# cpu.net
KiCad netlist of a schematic drawn in EAGLE
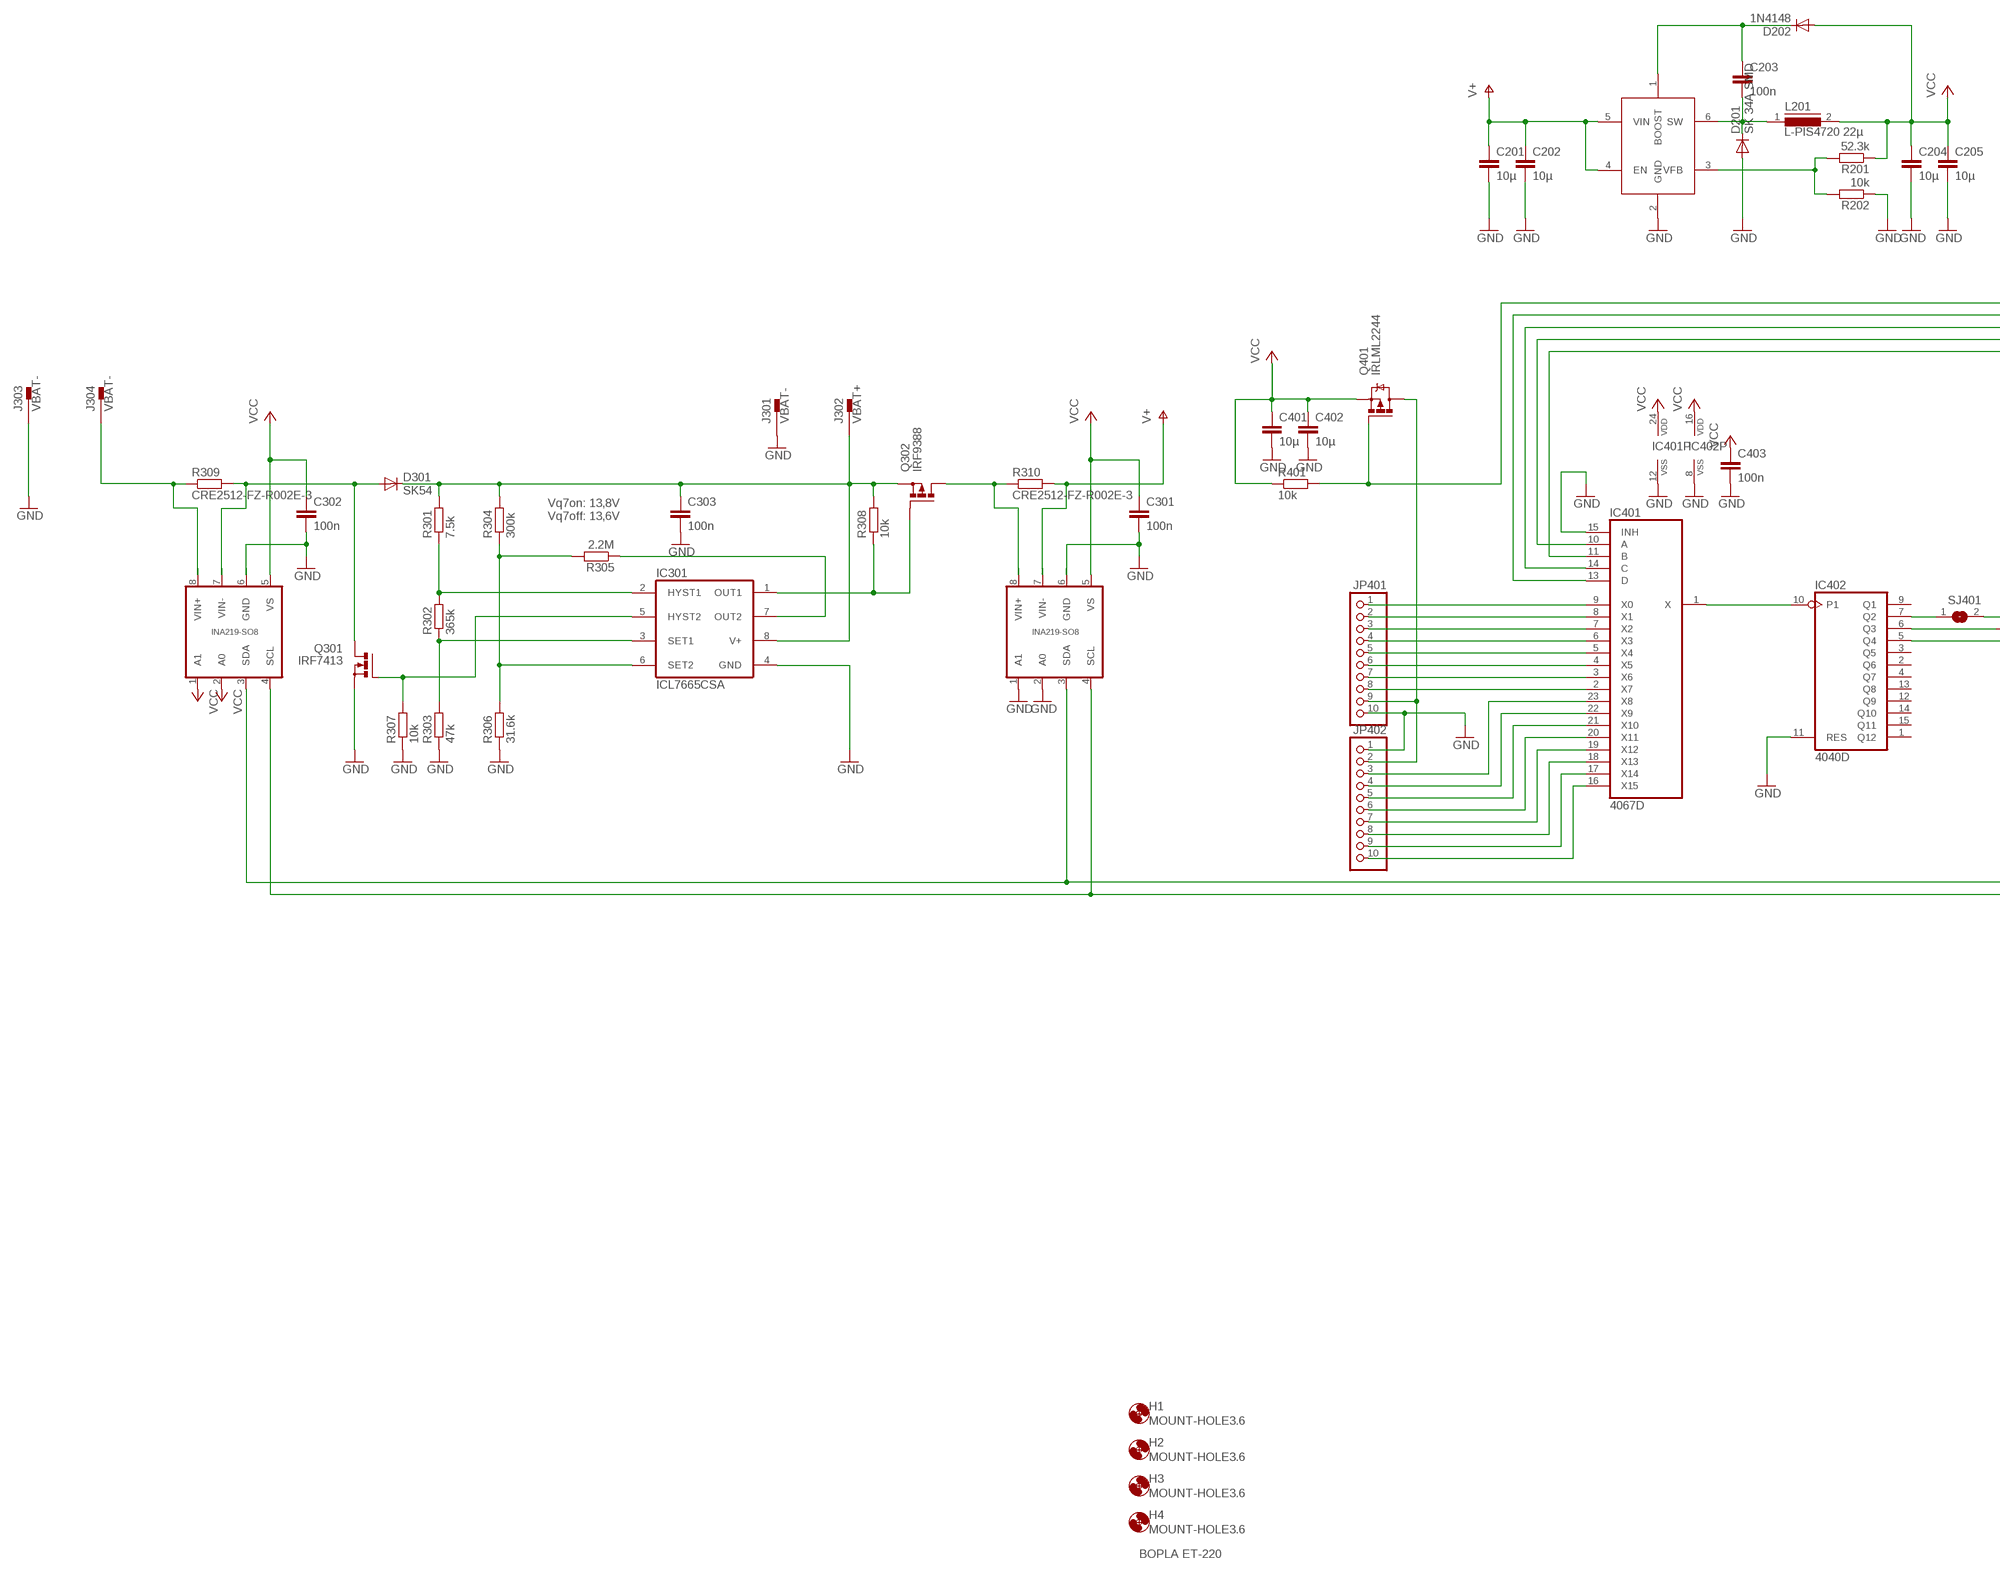
[diagram p0: schematic, sheet 1, part 1 of 2]
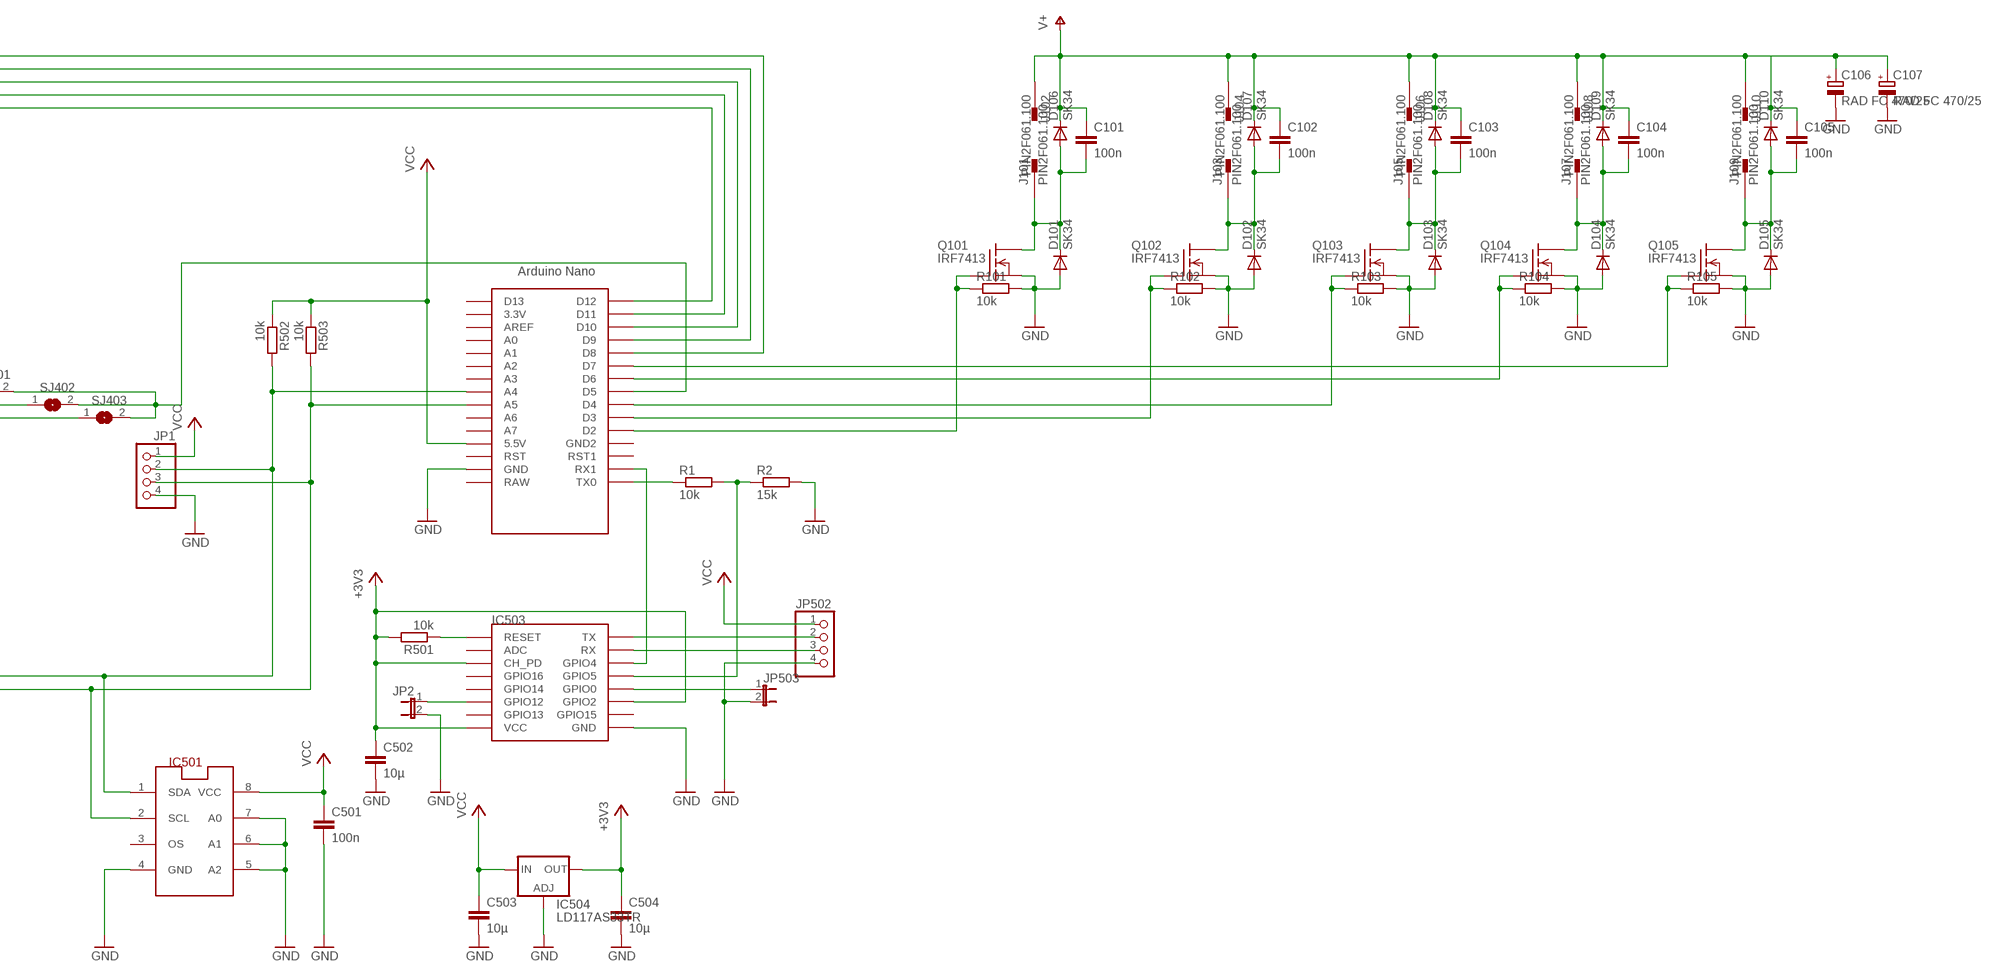
[diagram p1: schematic, sheet 1, part 2 of 2]

(export (version "E")
  (design (tool "Eeschema 10.0.6"))
  (components
    (comp (ref "C101")
      (value "100n")
      (footprint "eagle-import:C1206")
      (libsource (lib "eagle-import") (part "C-EUC1206"))
    )
    (comp (ref "C102")
      (value "100n")
      (footprint "eagle-import:C1206")
      (libsource (lib "eagle-import") (part "C-EUC1206"))
    )
    (comp (ref "C103")
      (value "100n")
      (footprint "eagle-import:C1206")
      (libsource (lib "eagle-import") (part "C-EUC1206"))
    )
    (comp (ref "C104")
      (value "100n")
      (footprint "eagle-import:C1206")
      (libsource (lib "eagle-import") (part "C-EUC1206"))
    )
    (comp (ref "C105")
      (value "100n")
      (footprint "eagle-import:C1206")
      (libsource (lib "eagle-import") (part "C-EUC1206"))
    )
    (comp (ref "C106")
      (value "RAD FC 470/25")
      (footprint "eagle-import:E3,5-8")
      (libsource (lib "eagle-import") (part "CPOL-EUE3.5-8"))
    )
    (comp (ref "C107")
      (value "RAD FC 470/25")
      (footprint "eagle-import:E3,5-8")
      (libsource (lib "eagle-import") (part "CPOL-EUE3.5-8"))
    )
    (comp (ref "C201")
      (value "10µ")
      (footprint "eagle-import:C1206")
      (libsource (lib "eagle-import") (part "C-EUC1206"))
    )
    (comp (ref "C202")
      (value "10µ")
      (footprint "eagle-import:C1206")
      (libsource (lib "eagle-import") (part "C-EUC1206"))
    )
    (comp (ref "C203")
      (value "100n")
      (footprint "eagle-import:C1206")
      (libsource (lib "eagle-import") (part "C-EUC1206"))
    )
    (comp (ref "C204")
      (value "10µ")
      (footprint "eagle-import:C1206")
      (libsource (lib "eagle-import") (part "C-EUC1206"))
    )
    (comp (ref "C205")
      (value "10µ")
      (footprint "eagle-import:C1206")
      (libsource (lib "eagle-import") (part "C-EUC1206"))
    )
    (comp (ref "C301")
      (value "100n")
      (footprint "eagle-import:C1206")
      (libsource (lib "eagle-import") (part "C-EUC1206"))
    )
    (comp (ref "C302")
      (value "100n")
      (footprint "eagle-import:C1206")
      (libsource (lib "eagle-import") (part "C-EUC1206"))
    )
    (comp (ref "C303")
      (value "100n")
      (footprint "eagle-import:C1206")
      (libsource (lib "eagle-import") (part "C-EUC1206"))
    )
    (comp (ref "C401")
      (value "10µ")
      (footprint "eagle-import:C1206")
      (libsource (lib "eagle-import") (part "C-EUC1206"))
    )
    (comp (ref "C402")
      (value "10µ")
      (footprint "eagle-import:C1206")
      (libsource (lib "eagle-import") (part "C-EUC1206"))
    )
    (comp (ref "C403")
      (value "100n")
      (footprint "eagle-import:C1206")
      (libsource (lib "eagle-import") (part "C-EUC1206"))
    )
    (comp (ref "C501")
      (value "100n")
      (footprint "eagle-import:C1206")
      (libsource (lib "eagle-import") (part "C-EUC1206"))
    )
    (comp (ref "C502")
      (value "10µ")
      (footprint "eagle-import:C1206")
      (libsource (lib "eagle-import") (part "C-EUC1206"))
    )
    (comp (ref "C503")
      (value "10µ")
      (footprint "eagle-import:C1206")
      (libsource (lib "eagle-import") (part "C-EUC1206"))
    )
    (comp (ref "C504")
      (value "10µ")
      (footprint "eagle-import:C1206")
      (libsource (lib "eagle-import") (part "C-EUC1206"))
    )
    (comp (ref "D101")
      (value "SK34")
      (footprint "eagle-import:DO214BA")
      (libsource (lib "eagle-import") (part "DIODE-DO214BA"))
    )
    (comp (ref "D102")
      (value "SK34")
      (footprint "eagle-import:DO214BA")
      (libsource (lib "eagle-import") (part "DIODE-DO214BA"))
    )
    (comp (ref "D103")
      (value "SK34")
      (footprint "eagle-import:DO214BA")
      (libsource (lib "eagle-import") (part "DIODE-DO214BA"))
    )
    (comp (ref "D104")
      (value "SK34")
      (footprint "eagle-import:DO214BA")
      (libsource (lib "eagle-import") (part "DIODE-DO214BA"))
    )
    (comp (ref "D105")
      (value "SK34")
      (footprint "eagle-import:DO214BA")
      (libsource (lib "eagle-import") (part "DIODE-DO214BA"))
    )
    (comp (ref "D106")
      (value "SK34")
      (footprint "eagle-import:DO214BA")
      (libsource (lib "eagle-import") (part "DIODE-DO214BA"))
    )
    (comp (ref "D107")
      (value "SK34")
      (footprint "eagle-import:DO214BA")
      (libsource (lib "eagle-import") (part "DIODE-DO214BA"))
    )
    (comp (ref "D108")
      (value "SK34")
      (footprint "eagle-import:DO214BA")
      (libsource (lib "eagle-import") (part "DIODE-DO214BA"))
    )
    (comp (ref "D109")
      (value "SK34")
      (footprint "eagle-import:DO214BA")
      (libsource (lib "eagle-import") (part "DIODE-DO214BA"))
    )
    (comp (ref "D110")
      (value "SK34")
      (footprint "eagle-import:DO214BA")
      (libsource (lib "eagle-import") (part "DIODE-DO214BA"))
    )
    (comp (ref "D201")
      (value "SK 34A SMD")
      (footprint "eagle-import:DO214BA")
      (libsource (lib "eagle-import") (part "DIODE-DO214BA"))
    )
    (comp (ref "D202")
      (value "1N4148")
      (footprint "eagle-import:MINIMELF")
      (libsource (lib "eagle-import") (part "DIODE-MINIMELF"))
    )
    (comp (ref "D301")
      (value "SK54")
      (footprint "eagle-import:SMC")
      (libsource (lib "eagle-import") (part "DIODE-SMC"))
    )
    (comp (ref "H1")
      (value "MOUNT-HOLE3.6")
      (footprint "eagle-import:3,6")
      (libsource (lib "eagle-import") (part "MOUNT-HOLE3.6"))
    )
    (comp (ref "H2")
      (value "MOUNT-HOLE3.6")
      (footprint "eagle-import:3,6")
      (libsource (lib "eagle-import") (part "MOUNT-HOLE3.6"))
    )
    (comp (ref "H3")
      (value "MOUNT-HOLE3.6")
      (footprint "eagle-import:3,6")
      (libsource (lib "eagle-import") (part "MOUNT-HOLE3.6"))
    )
    (comp (ref "H4")
      (value "MOUNT-HOLE3.6")
      (footprint "eagle-import:3,6")
      (libsource (lib "eagle-import") (part "MOUNT-HOLE3.6"))
    )
    (comp (ref "IC201")
      (value "MCP16301/H")
      (footprint "eagle-import:SOT23-6")
      (libsource (lib "eagle-import") (part "MCP16301/H"))
    )
    (comp (ref "IC301")
      (value "ICL7665CSA")
      (footprint "eagle-import:SO08")
      (fields (field (name "MPN") "ICL7665CSA+"))
      (libsource (lib "eagle-import") (part "ICL7665CSA"))
    )
    (comp (ref "IC302")
      (value "INA219-SO8D")
      (footprint "eagle-import:SO08")
      (libsource (lib "eagle-import") (part "INA219-SO8D"))
    )
    (comp (ref "IC303")
      (value "INA219-SO8D")
      (footprint "eagle-import:SO08")
      (libsource (lib "eagle-import") (part "INA219-SO8D"))
    )
    (comp (ref "IC401")
      (value "4067D")
      (footprint "eagle-import:SO24W")
      (libsource (lib "eagle-import") (part "4067D"))
    )
    (comp (ref "IC402")
      (value "4040D")
      (footprint "eagle-import:SO16")
      (libsource (lib "eagle-import") (part "4040D"))
    )
    (comp (ref "IC501")
      (value "LM75_ICN")
      (footprint "eagle-import:SO8_LM75")
      (libsource (lib "eagle-import") (part "LM75_ICN"))
    )
    (comp (ref "IC502")
      (value "NANO")
      (footprint "eagle-import:NANO")
      (libsource (lib "eagle-import") (part "NANO"))
    )
    (comp (ref "IC503")
      (value "ESP12SMD")
      (footprint "eagle-import:ESP12-SMD")
      (libsource (lib "eagle-import") (part "ESP12SMD"))
    )
    (comp (ref "IC504")
      (value "LD117AS33TR")
      (footprint "eagle-import:SOT223")
      (libsource (lib "eagle-import") (part "LD117A?S33TR"))
    )
    (comp (ref "J101")
      (value "PIN2F061.100")
      (footprint "eagle-import:F061.100")
      (libsource (lib "eagle-import") (part "PIN2F061.100"))
    )
    (comp (ref "J102")
      (value "PIN2F061.100")
      (footprint "eagle-import:F061.100")
      (fields (field (name "OC_FARNELL") "unknown") (field (name "OC_NEWARK") "unknown"))
      (libsource (lib "eagle-import") (part "PIN2F061.100"))
    )
    (comp (ref "J103")
      (value "PIN2F061.100")
      (footprint "eagle-import:F061.100")
      (libsource (lib "eagle-import") (part "PIN2F061.100"))
    )
    (comp (ref "J104")
      (value "PIN2F061.100")
      (footprint "eagle-import:F061.100")
      (fields (field (name "OC_FARNELL") "unknown") (field (name "OC_NEWARK") "unknown"))
      (libsource (lib "eagle-import") (part "PIN2F061.100"))
    )
    (comp (ref "J105")
      (value "PIN2F061.100")
      (footprint "eagle-import:F061.100")
      (libsource (lib "eagle-import") (part "PIN2F061.100"))
    )
    (comp (ref "J106")
      (value "PIN2F061.100")
      (footprint "eagle-import:F061.100")
      (fields (field (name "OC_FARNELL") "unknown") (field (name "OC_NEWARK") "unknown"))
      (libsource (lib "eagle-import") (part "PIN2F061.100"))
    )
    (comp (ref "J107")
      (value "PIN2F061.100")
      (footprint "eagle-import:F061.100")
      (libsource (lib "eagle-import") (part "PIN2F061.100"))
    )
    (comp (ref "J108")
      (value "PIN2F061.100")
      (footprint "eagle-import:F061.100")
      (fields (field (name "OC_FARNELL") "unknown") (field (name "OC_NEWARK") "unknown"))
      (libsource (lib "eagle-import") (part "PIN2F061.100"))
    )
    (comp (ref "J109")
      (value "PIN2F061.100")
      (footprint "eagle-import:F061.100")
      (libsource (lib "eagle-import") (part "PIN2F061.100"))
    )
    (comp (ref "J110")
      (value "PIN2F061.100")
      (footprint "eagle-import:F061.100")
      (fields (field (name "OC_FARNELL") "unknown") (field (name "OC_NEWARK") "unknown"))
      (libsource (lib "eagle-import") (part "PIN2F061.100"))
    )
    (comp (ref "J301")
      (value "VBAT-")
      (footprint "eagle-import:F061.100")
      (fields (field (name "OC_FARNELL") "unknown") (field (name "OC_NEWARK") "unknown"))
      (libsource (lib "eagle-import") (part "PIN2F061.100"))
    )
    (comp (ref "J302")
      (value "VBAT+")
      (footprint "eagle-import:F061.100")
      (fields (field (name "OC_FARNELL") "unknown") (field (name "OC_NEWARK") "unknown"))
      (libsource (lib "eagle-import") (part "PIN2F061.100"))
    )
    (comp (ref "J303")
      (value "VBAT-")
      (footprint "eagle-import:F061.100")
      (fields (field (name "OC_FARNELL") "unknown") (field (name "OC_NEWARK") "unknown"))
      (libsource (lib "eagle-import") (part "PIN2F061.100"))
    )
    (comp (ref "J304")
      (value "VBAT-")
      (footprint "eagle-import:F061.100")
      (fields (field (name "OC_FARNELL") "unknown") (field (name "OC_NEWARK") "unknown"))
      (libsource (lib "eagle-import") (part "PIN2F061.100"))
    )
    (comp (ref "JP1")
      (value "PINHD-1X4")
      (footprint "eagle-import:1X04")
      (libsource (lib "eagle-import") (part "PINHD-1X4"))
    )
    (comp (ref "JP2")
      (value "JP1E")
      (footprint "eagle-import:JP1")
      (libsource (lib "eagle-import") (part "JP1E"))
    )
    (comp (ref "JP401")
      (value "PINHD-1X10")
      (footprint "eagle-import:1X10")
      (libsource (lib "eagle-import") (part "PINHD-1X10"))
    )
    (comp (ref "JP402")
      (value "PINHD-1X10")
      (footprint "eagle-import:1X10")
      (libsource (lib "eagle-import") (part "PINHD-1X10"))
    )
    (comp (ref "JP502")
      (value "PINHD-1X4")
      (footprint "eagle-import:1X04")
      (libsource (lib "eagle-import") (part "PINHD-1X4"))
    )
    (comp (ref "JP503")
      (value "JP1E")
      (footprint "eagle-import:JP1")
      (libsource (lib "eagle-import") (part "JP1E"))
    )
    (comp (ref "L201")
      (value "L-PIS4720 22µ")
      (footprint "eagle-import:DR74")
      (libsource (lib "eagle-import") (part "DR74"))
    )
    (comp (ref "Q101")
      (value "IRF7413")
      (footprint "eagle-import:SO-8")
      (libsource (lib "eagle-import") (part "FDS5680"))
    )
    (comp (ref "Q102")
      (value "IRF7413")
      (footprint "eagle-import:SO-8")
      (libsource (lib "eagle-import") (part "FDS5680"))
    )
    (comp (ref "Q103")
      (value "IRF7413")
      (footprint "eagle-import:SO-8")
      (libsource (lib "eagle-import") (part "FDS5680"))
    )
    (comp (ref "Q104")
      (value "IRF7413")
      (footprint "eagle-import:SO-8")
      (libsource (lib "eagle-import") (part "FDS5680"))
    )
    (comp (ref "Q105")
      (value "IRF7413")
      (footprint "eagle-import:SO-8")
      (libsource (lib "eagle-import") (part "FDS5680"))
    )
    (comp (ref "Q301")
      (value "IRF7413")
      (footprint "eagle-import:SO-08")
      (libsource (lib "eagle-import") (part "N-MOSFET-SO8S"))
    )
    (comp (ref "Q302")
      (value "IRF9388")
      (footprint "eagle-import:SO-08")
      (libsource (lib "eagle-import") (part "P-MOSFET-SO8"))
    )
    (comp (ref "Q401")
      (value "IRLML2244")
      (footprint "eagle-import:MICRO3")
      (libsource (lib "eagle-import") (part "IRLML5203"))
    )
    (comp (ref "R1")
      (value "10k")
      (footprint "eagle-import:R0805")
      (libsource (lib "eagle-import") (part "R-EU_R0805"))
    )
    (comp (ref "R2")
      (value "15k")
      (footprint "eagle-import:R0805")
      (libsource (lib "eagle-import") (part "R-EU_R0805"))
    )
    (comp (ref "R101")
      (value "10k")
      (footprint "eagle-import:R0805")
      (libsource (lib "eagle-import") (part "R-EU_R0805"))
    )
    (comp (ref "R102")
      (value "10k")
      (footprint "eagle-import:R0805")
      (libsource (lib "eagle-import") (part "R-EU_R0805"))
    )
    (comp (ref "R103")
      (value "10k")
      (footprint "eagle-import:R0805")
      (libsource (lib "eagle-import") (part "R-EU_R0805"))
    )
    (comp (ref "R104")
      (value "10k")
      (footprint "eagle-import:R0805")
      (libsource (lib "eagle-import") (part "R-EU_R0805"))
    )
    (comp (ref "R105")
      (value "10k")
      (footprint "eagle-import:R0805")
      (libsource (lib "eagle-import") (part "R-EU_R0805"))
    )
    (comp (ref "R201")
      (value "52.3k")
      (footprint "eagle-import:R0805")
      (libsource (lib "eagle-import") (part "R-EU_R0805"))
    )
    (comp (ref "R202")
      (value "10k")
      (footprint "eagle-import:R0805")
      (libsource (lib "eagle-import") (part "R-EU_R0805"))
    )
    (comp (ref "R301")
      (value "7.5k")
      (footprint "eagle-import:R0805")
      (libsource (lib "eagle-import") (part "R-EU_R0805"))
    )
    (comp (ref "R302")
      (value "365k")
      (footprint "eagle-import:R0805")
      (libsource (lib "eagle-import") (part "R-EU_R0805"))
    )
    (comp (ref "R303")
      (value "47k")
      (footprint "eagle-import:R0805")
      (libsource (lib "eagle-import") (part "R-EU_R0805"))
    )
    (comp (ref "R304")
      (value "300k")
      (footprint "eagle-import:R0805")
      (libsource (lib "eagle-import") (part "R-EU_R0805"))
    )
    (comp (ref "R305")
      (value "2.2M")
      (footprint "eagle-import:R0805")
      (libsource (lib "eagle-import") (part "R-EU_R0805"))
    )
    (comp (ref "R306")
      (value "31.6k")
      (footprint "eagle-import:R0805")
      (libsource (lib "eagle-import") (part "R-EU_R0805"))
    )
    (comp (ref "R307")
      (value "10k")
      (footprint "eagle-import:R0805")
      (libsource (lib "eagle-import") (part "R-EU_R0805"))
    )
    (comp (ref "R308")
      (value "10k")
      (footprint "eagle-import:R0805")
      (libsource (lib "eagle-import") (part "R-EU_R0805"))
    )
    (comp (ref "R309")
      (value "CRE2512-FZ-R002E-3")
      (footprint "eagle-import:R2512")
      (libsource (lib "eagle-import") (part "R-EU_R2512"))
    )
    (comp (ref "R310")
      (value "CRE2512-FZ-R002E-3")
      (footprint "eagle-import:R2512")
      (libsource (lib "eagle-import") (part "R-EU_R2512"))
    )
    (comp (ref "R401")
      (value "10k")
      (footprint "eagle-import:R0805")
      (libsource (lib "eagle-import") (part "R-EU_R0805"))
    )
    (comp (ref "R501")
      (value "10k")
      (footprint "eagle-import:R0805")
      (libsource (lib "eagle-import") (part "R-EU_R0805"))
    )
    (comp (ref "R502")
      (value "10k")
      (footprint "eagle-import:R0805")
      (libsource (lib "eagle-import") (part "R-EU_R0805"))
    )
    (comp (ref "R503")
      (value "10k")
      (footprint "eagle-import:R0805")
      (libsource (lib "eagle-import") (part "R-EU_R0805"))
    )
    (comp (ref "SJ401")
      (value "SJW")
      (footprint "eagle-import:SJW")
      (libsource (lib "eagle-import") (part "SJW"))
    )
    (comp (ref "SJ402")
      (value "SJW")
      (footprint "eagle-import:SJW")
      (libsource (lib "eagle-import") (part "SJW"))
    )
    (comp (ref "SJ403")
      (value "SJW")
      (footprint "eagle-import:SJW")
      (libsource (lib "eagle-import") (part "SJW"))
    )
  )
  (nets
    (net (code "1") (name "+3V3") (class "Default")
      (node (ref "C502") (pin "1") (pinfunction "1_1") (pintype "passive"))
      (node (ref "C504") (pin "1") (pinfunction "1_1") (pintype "passive"))
      (node (ref "IC503") (pin "CH_PD") (pinfunction "CH_PD_CH_PD") (pintype "bidirectional"))
      (node (ref "IC503") (pin "GPIO2") (pinfunction "GPIO2_GPIO2") (pintype "bidirectional"))
      (node (ref "IC503") (pin "VCC") (pinfunction "VCC_VCC") (pintype "bidirectional"))
      (node (ref "IC504") (pin "4") (pinfunction "OUT_4") (pintype "passive"))
      (node (ref "R501") (pin "2") (pinfunction "2_2") (pintype "passive"))
    )
    (net (code "2") (name "GND") (class "Default")
      (node (ref "C106") (pin "-") (pinfunction "-_-") (pintype "passive"))
      (node (ref "C107") (pin "-") (pinfunction "-_-") (pintype "passive"))
      (node (ref "C201") (pin "2") (pinfunction "2_2") (pintype "passive"))
      (node (ref "C202") (pin "2") (pinfunction "2_2") (pintype "passive"))
      (node (ref "C204") (pin "2") (pinfunction "2_2") (pintype "passive"))
      (node (ref "C205") (pin "2") (pinfunction "2_2") (pintype "passive"))
      (node (ref "C301") (pin "2") (pinfunction "2_2") (pintype "passive"))
      (node (ref "C302") (pin "2") (pinfunction "2_2") (pintype "passive"))
      (node (ref "C303") (pin "2") (pinfunction "2_2") (pintype "passive"))
      (node (ref "C401") (pin "2") (pinfunction "2_2") (pintype "passive"))
      (node (ref "C402") (pin "2") (pinfunction "2_2") (pintype "passive"))
      (node (ref "C403") (pin "2") (pinfunction "2_2") (pintype "passive"))
      (node (ref "C501") (pin "2") (pinfunction "2_2") (pintype "passive"))
      (node (ref "C502") (pin "2") (pinfunction "2_2") (pintype "passive"))
      (node (ref "C503") (pin "2") (pinfunction "2_2") (pintype "passive"))
      (node (ref "C504") (pin "2") (pinfunction "2_2") (pintype "passive"))
      (node (ref "D101") (pin "A") (pinfunction "A_A") (pintype "passive"))
      (node (ref "D102") (pin "A") (pinfunction "A_A") (pintype "passive"))
      (node (ref "D103") (pin "A") (pinfunction "A_A") (pintype "passive"))
      (node (ref "D104") (pin "A") (pinfunction "A_A") (pintype "passive"))
      (node (ref "D105") (pin "A") (pinfunction "A_A") (pintype "passive"))
      (node (ref "D201") (pin "A") (pinfunction "A_A") (pintype "passive"))
      (node (ref "IC201") (pin "2") (pinfunction "GND_2") (pintype "power_in"))
      (node (ref "IC301") (pin "4") (pinfunction "GND_4") (pintype "power_in"))
      (node (ref "IC302") (pin "6") (pinfunction "GND_6") (pintype "power_in"))
      (node (ref "IC303") (pin "1") (pinfunction "A1_1") (pintype "input"))
      (node (ref "IC303") (pin "2") (pinfunction "A0_2") (pintype "input"))
      (node (ref "IC303") (pin "6") (pinfunction "GND_6") (pintype "power_in"))
      (node (ref "IC401") (pin "12") (pinfunction "VSS_12") (pintype "power_in"))
      (node (ref "IC401") (pin "15") (pinfunction "INH_15") (pintype "input"))
      (node (ref "IC402") (pin "11") (pinfunction "RES_11") (pintype "input"))
      (node (ref "IC402") (pin "8") (pinfunction "VSS_8") (pintype "power_in"))
      (node (ref "IC501") (pin "4") (pinfunction "GND_4") (pintype "power_in"))
      (node (ref "IC501") (pin "5") (pinfunction "A2_5") (pintype "input"))
      (node (ref "IC501") (pin "6") (pinfunction "A1_6") (pintype "input"))
      (node (ref "IC501") (pin "7") (pinfunction "A0_7") (pintype "input"))
      (node (ref "IC502") (pin "GND") (pinfunction "GND_GND") (pintype "bidirectional"))
      (node (ref "IC503") (pin "GND") (pinfunction "GND_GND") (pintype "bidirectional"))
      (node (ref "IC504") (pin "1") (pinfunction "ADJ_1") (pintype "input"))
      (node (ref "J301") (pin "A1") (pinfunction "1_A1") (pintype "passive"))
      (node (ref "J301") (pin "A2") (pinfunction "1_A2") (pintype "passive"))
      (node (ref "J303") (pin "A1") (pinfunction "1_A1") (pintype "passive"))
      (node (ref "J303") (pin "A2") (pinfunction "1_A2") (pintype "passive"))
      (node (ref "JP1") (pin "4") (pinfunction "4_4") (pintype "passive"))
      (node (ref "JP2") (pin "2") (pinfunction "2_2") (pintype "passive"))
      (node (ref "JP401") (pin "10") (pinfunction "10_10") (pintype "passive"))
      (node (ref "JP402") (pin "1") (pinfunction "1_1") (pintype "passive"))
      (node (ref "JP502") (pin "4") (pinfunction "4_4") (pintype "passive"))
      (node (ref "JP503") (pin "2") (pinfunction "2_2") (pintype "passive"))
      (node (ref "Q101") (pin "1") (pinfunction "S_1") (pintype "passive"))
      (node (ref "Q101") (pin "2") (pinfunction "S_2") (pintype "passive"))
      (node (ref "Q101") (pin "3") (pinfunction "S_3") (pintype "passive"))
      (node (ref "Q102") (pin "1") (pinfunction "S_1") (pintype "passive"))
      (node (ref "Q102") (pin "2") (pinfunction "S_2") (pintype "passive"))
      (node (ref "Q102") (pin "3") (pinfunction "S_3") (pintype "passive"))
      (node (ref "Q103") (pin "1") (pinfunction "S_1") (pintype "passive"))
      (node (ref "Q103") (pin "2") (pinfunction "S_2") (pintype "passive"))
      (node (ref "Q103") (pin "3") (pinfunction "S_3") (pintype "passive"))
      (node (ref "Q104") (pin "1") (pinfunction "S_1") (pintype "passive"))
      (node (ref "Q104") (pin "2") (pinfunction "S_2") (pintype "passive"))
      (node (ref "Q104") (pin "3") (pinfunction "S_3") (pintype "passive"))
      (node (ref "Q105") (pin "1") (pinfunction "S_1") (pintype "passive"))
      (node (ref "Q105") (pin "2") (pinfunction "S_2") (pintype "passive"))
      (node (ref "Q105") (pin "3") (pinfunction "S_3") (pintype "passive"))
      (node (ref "Q301") (pin "1") (pinfunction "S_1") (pintype "passive"))
      (node (ref "Q301") (pin "2") (pinfunction "S_2") (pintype "passive"))
      (node (ref "Q301") (pin "3") (pinfunction "S_3") (pintype "passive"))
      (node (ref "R101") (pin "2") (pinfunction "2_2") (pintype "passive"))
      (node (ref "R102") (pin "2") (pinfunction "2_2") (pintype "passive"))
      (node (ref "R103") (pin "2") (pinfunction "2_2") (pintype "passive"))
      (node (ref "R104") (pin "2") (pinfunction "2_2") (pintype "passive"))
      (node (ref "R105") (pin "2") (pinfunction "2_2") (pintype "passive"))
      (node (ref "R2") (pin "2") (pinfunction "2_2") (pintype "passive"))
      (node (ref "R202") (pin "1") (pinfunction "1_1") (pintype "passive"))
      (node (ref "R303") (pin "1") (pinfunction "1_1") (pintype "passive"))
      (node (ref "R306") (pin "1") (pinfunction "1_1") (pintype "passive"))
      (node (ref "R307") (pin "1") (pinfunction "1_1") (pintype "passive"))
    )
    (net (code "3") (name "Net-(C101-Pad2)") (class "Default")
      (node (ref "C101") (pin "2") (pinfunction "2_2") (pintype "passive"))
      (node (ref "D101") (pin "C") (pinfunction "C_C") (pintype "passive"))
      (node (ref "D106") (pin "A") (pinfunction "A_A") (pintype "passive"))
      (node (ref "J101") (pin "A1") (pinfunction "1_A1") (pintype "passive"))
      (node (ref "J101") (pin "A2") (pinfunction "1_A2") (pintype "passive"))
      (node (ref "Q101") (pin "5") (pinfunction "D_5") (pintype "passive"))
      (node (ref "Q101") (pin "6") (pinfunction "D_6") (pintype "passive"))
      (node (ref "Q101") (pin "7") (pinfunction "D_7") (pintype "passive"))
      (node (ref "Q101") (pin "8") (pinfunction "D_8") (pintype "passive"))
    )
    (net (code "4") (name "Net-(C102-Pad2)") (class "Default")
      (node (ref "C102") (pin "2") (pinfunction "2_2") (pintype "passive"))
      (node (ref "D102") (pin "C") (pinfunction "C_C") (pintype "passive"))
      (node (ref "D107") (pin "A") (pinfunction "A_A") (pintype "passive"))
      (node (ref "J103") (pin "A1") (pinfunction "1_A1") (pintype "passive"))
      (node (ref "J103") (pin "A2") (pinfunction "1_A2") (pintype "passive"))
      (node (ref "Q102") (pin "5") (pinfunction "D_5") (pintype "passive"))
      (node (ref "Q102") (pin "6") (pinfunction "D_6") (pintype "passive"))
      (node (ref "Q102") (pin "7") (pinfunction "D_7") (pintype "passive"))
      (node (ref "Q102") (pin "8") (pinfunction "D_8") (pintype "passive"))
    )
    (net (code "5") (name "Net-(C103-Pad2)") (class "Default")
      (node (ref "C103") (pin "2") (pinfunction "2_2") (pintype "passive"))
      (node (ref "D103") (pin "C") (pinfunction "C_C") (pintype "passive"))
      (node (ref "D108") (pin "A") (pinfunction "A_A") (pintype "passive"))
      (node (ref "J105") (pin "A1") (pinfunction "1_A1") (pintype "passive"))
      (node (ref "J105") (pin "A2") (pinfunction "1_A2") (pintype "passive"))
      (node (ref "Q103") (pin "5") (pinfunction "D_5") (pintype "passive"))
      (node (ref "Q103") (pin "6") (pinfunction "D_6") (pintype "passive"))
      (node (ref "Q103") (pin "7") (pinfunction "D_7") (pintype "passive"))
      (node (ref "Q103") (pin "8") (pinfunction "D_8") (pintype "passive"))
    )
    (net (code "6") (name "Net-(C104-Pad2)") (class "Default")
      (node (ref "C104") (pin "2") (pinfunction "2_2") (pintype "passive"))
      (node (ref "D104") (pin "C") (pinfunction "C_C") (pintype "passive"))
      (node (ref "D109") (pin "A") (pinfunction "A_A") (pintype "passive"))
      (node (ref "J107") (pin "A1") (pinfunction "1_A1") (pintype "passive"))
      (node (ref "J107") (pin "A2") (pinfunction "1_A2") (pintype "passive"))
      (node (ref "Q104") (pin "5") (pinfunction "D_5") (pintype "passive"))
      (node (ref "Q104") (pin "6") (pinfunction "D_6") (pintype "passive"))
      (node (ref "Q104") (pin "7") (pinfunction "D_7") (pintype "passive"))
      (node (ref "Q104") (pin "8") (pinfunction "D_8") (pintype "passive"))
    )
    (net (code "7") (name "Net-(C105-Pad2)") (class "Default")
      (node (ref "C105") (pin "2") (pinfunction "2_2") (pintype "passive"))
      (node (ref "D105") (pin "C") (pinfunction "C_C") (pintype "passive"))
      (node (ref "D110") (pin "A") (pinfunction "A_A") (pintype "passive"))
      (node (ref "J109") (pin "A1") (pinfunction "1_A1") (pintype "passive"))
      (node (ref "J109") (pin "A2") (pinfunction "1_A2") (pintype "passive"))
      (node (ref "Q105") (pin "5") (pinfunction "D_5") (pintype "passive"))
      (node (ref "Q105") (pin "6") (pinfunction "D_6") (pintype "passive"))
      (node (ref "Q105") (pin "7") (pinfunction "D_7") (pintype "passive"))
      (node (ref "Q105") (pin "8") (pinfunction "D_8") (pintype "passive"))
    )
    (net (code "8") (name "Net-(IC201-BOOST)") (class "Default")
      (node (ref "C203") (pin "1") (pinfunction "1_1") (pintype "passive"))
      (node (ref "D202") (pin "C") (pinfunction "C_C") (pintype "passive"))
      (node (ref "IC201") (pin "1") (pinfunction "BOOST_1") (pintype "bidirectional"))
    )
    (net (code "9") (name "Net-(IC201-SW)") (class "Default")
      (node (ref "C203") (pin "2") (pinfunction "2_2") (pintype "passive"))
      (node (ref "D201") (pin "C") (pinfunction "C_C") (pintype "passive"))
      (node (ref "IC201") (pin "6") (pinfunction "SW_6") (pintype "power_in"))
      (node (ref "L201") (pin "1") (pinfunction "1_1") (pintype "passive"))
    )
    (net (code "10") (name "Net-(IC201-VFB)") (class "Default")
      (node (ref "IC201") (pin "3") (pinfunction "VFB_3") (pintype "bidirectional"))
      (node (ref "R201") (pin "2") (pinfunction "2_2") (pintype "passive"))
      (node (ref "R202") (pin "2") (pinfunction "2_2") (pintype "passive"))
    )
    (net (code "11") (name "Net-(IC301-HYST1)") (class "Default")
      (node (ref "IC301") (pin "2") (pinfunction "HYST1_2") (pintype "input"))
      (node (ref "R301") (pin "1") (pinfunction "1_1") (pintype "passive"))
      (node (ref "R302") (pin "2") (pinfunction "2_2") (pintype "passive"))
    )
    (net (code "12") (name "Net-(IC301-HYST2)") (class "Default")
      (node (ref "IC301") (pin "5") (pinfunction "HYST2_5") (pintype "input"))
      (node (ref "Q301") (pin "4") (pinfunction "G_4") (pintype "passive"))
      (node (ref "R307") (pin "2") (pinfunction "2_2") (pintype "passive"))
    )
    (net (code "13") (name "Net-(IC301-OUT1)") (class "Default")
      (node (ref "IC301") (pin "1") (pinfunction "OUT1_1") (pintype "output"))
      (node (ref "Q302") (pin "4") (pinfunction "G_4") (pintype "passive"))
      (node (ref "R308") (pin "1") (pinfunction "1_1") (pintype "passive"))
    )
    (net (code "14") (name "Net-(IC301-OUT2)") (class "Default")
      (node (ref "IC301") (pin "7") (pinfunction "OUT2_7") (pintype "output"))
      (node (ref "R305") (pin "1") (pinfunction "1_1") (pintype "passive"))
    )
    (net (code "15") (name "Net-(IC301-SET1)") (class "Default")
      (node (ref "IC301") (pin "3") (pinfunction "SET1_3") (pintype "input"))
      (node (ref "R302") (pin "1") (pinfunction "1_1") (pintype "passive"))
      (node (ref "R303") (pin "2") (pinfunction "2_2") (pintype "passive"))
    )
    (net (code "16") (name "Net-(IC301-SET2)") (class "Default")
      (node (ref "IC301") (pin "6") (pinfunction "SET2_6") (pintype "input"))
      (node (ref "R304") (pin "1") (pinfunction "1_1") (pintype "passive"))
      (node (ref "R305") (pin "2") (pinfunction "2_2") (pintype "passive"))
      (node (ref "R306") (pin "2") (pinfunction "2_2") (pintype "passive"))
    )
    (net (code "17") (name "Net-(IC301-V+)") (class "Default")
      (node (ref "C303") (pin "1") (pinfunction "1_1") (pintype "passive"))
      (node (ref "D301") (pin "C") (pinfunction "C_C") (pintype "passive"))
      (node (ref "IC301") (pin "8") (pinfunction "V+_8") (pintype "power_in"))
      (node (ref "J302") (pin "A1") (pinfunction "1_A1") (pintype "passive"))
      (node (ref "J302") (pin "A2") (pinfunction "1_A2") (pintype "passive"))
      (node (ref "Q302") (pin "1") (pinfunction "S_1") (pintype "passive"))
      (node (ref "Q302") (pin "2") (pinfunction "S_2") (pintype "passive"))
      (node (ref "Q302") (pin "3") (pinfunction "S_3") (pintype "passive"))
      (node (ref "R301") (pin "2") (pinfunction "2_2") (pintype "passive"))
      (node (ref "R304") (pin "2") (pinfunction "2_2") (pintype "passive"))
      (node (ref "R308") (pin "2") (pinfunction "2_2") (pintype "passive"))
    )
    (net (code "18") (name "Net-(IC302-SCL)") (class "Default")
      (node (ref "IC302") (pin "4") (pinfunction "SCL_4") (pintype "bidirectional"))
      (node (ref "IC303") (pin "4") (pinfunction "SCL_4") (pintype "bidirectional"))
      (node (ref "IC501") (pin "2") (pinfunction "SCL_2") (pintype "bidirectional"))
      (node (ref "IC502") (pin "A5") (pinfunction "A5_A5") (pintype "bidirectional"))
      (node (ref "JP1") (pin "3") (pinfunction "3_3") (pintype "passive"))
      (node (ref "R503") (pin "2") (pinfunction "2_2") (pintype "passive"))
    )
    (net (code "19") (name "Net-(IC302-SDA)") (class "Default")
      (node (ref "IC302") (pin "3") (pinfunction "SDA_3") (pintype "bidirectional"))
      (node (ref "IC303") (pin "3") (pinfunction "SDA_3") (pintype "bidirectional"))
      (node (ref "IC501") (pin "1") (pinfunction "SDA_1") (pintype "bidirectional"))
      (node (ref "IC502") (pin "A4") (pinfunction "A4_A4") (pintype "bidirectional"))
      (node (ref "JP1") (pin "2") (pinfunction "2_2") (pintype "passive"))
      (node (ref "R502") (pin "2") (pinfunction "2_2") (pintype "passive"))
    )
    (net (code "20") (name "Net-(IC302-VIN+)") (class "Default")
      (node (ref "IC302") (pin "8") (pinfunction "VIN+_8") (pintype "input"))
      (node (ref "J304") (pin "A1") (pinfunction "1_A1") (pintype "passive"))
      (node (ref "J304") (pin "A2") (pinfunction "1_A2") (pintype "passive"))
      (node (ref "R309") (pin "1") (pinfunction "1_1") (pintype "passive"))
    )
    (net (code "21") (name "Net-(IC302-VIN-)") (class "Default")
      (node (ref "D301") (pin "A") (pinfunction "A_A") (pintype "passive"))
      (node (ref "IC302") (pin "7") (pinfunction "VIN-_7") (pintype "input"))
      (node (ref "Q301") (pin "5") (pinfunction "D_5") (pintype "passive"))
      (node (ref "Q301") (pin "6") (pinfunction "D_6") (pintype "passive"))
      (node (ref "Q301") (pin "7") (pinfunction "D_7") (pintype "passive"))
      (node (ref "Q301") (pin "8") (pinfunction "D_8") (pintype "passive"))
      (node (ref "R309") (pin "2") (pinfunction "2_2") (pintype "passive"))
    )
    (net (code "22") (name "Net-(IC303-VIN+)") (class "Default")
      (node (ref "IC303") (pin "8") (pinfunction "VIN+_8") (pintype "input"))
      (node (ref "Q302") (pin "5") (pinfunction "D_5") (pintype "passive"))
      (node (ref "Q302") (pin "6") (pinfunction "D_6") (pintype "passive"))
      (node (ref "Q302") (pin "7") (pinfunction "D_7") (pintype "passive"))
      (node (ref "Q302") (pin "8") (pinfunction "D_8") (pintype "passive"))
      (node (ref "R310") (pin "1") (pinfunction "1_1") (pintype "passive"))
    )
    (net (code "23") (name "Net-(IC401A-A)") (class "Default")
      (node (ref "IC401") (pin "10") (pinfunction "A_10") (pintype "input"))
      (node (ref "IC502") (pin "D11") (pinfunction "D11_D11") (pintype "bidirectional"))
    )
    (net (code "24") (name "Net-(IC401A-B)") (class "Default")
      (node (ref "IC401") (pin "11") (pinfunction "B_11") (pintype "input"))
      (node (ref "IC502") (pin "D12") (pinfunction "D12_D12") (pintype "bidirectional"))
    )
    (net (code "25") (name "Net-(IC401A-C)") (class "Default")
      (node (ref "IC401") (pin "14") (pinfunction "C_14") (pintype "input"))
      (node (ref "IC502") (pin "D10") (pinfunction "D10_D10") (pintype "bidirectional"))
    )
    (net (code "26") (name "Net-(IC401A-D)") (class "Default")
      (node (ref "IC401") (pin "13") (pinfunction "D_13") (pintype "input"))
      (node (ref "IC502") (pin "D9") (pinfunction "D9_D9") (pintype "bidirectional"))
    )
    (net (code "27") (name "Net-(IC401A-X)") (class "Default")
      (node (ref "IC401") (pin "1") (pinfunction "X_1") (pintype "output"))
      (node (ref "IC402") (pin "10") (pinfunction "P1_10") (pintype "input"))
    )
    (net (code "28") (name "Net-(IC401A-X0)") (class "Default")
      (node (ref "IC401") (pin "9") (pinfunction "X0_9") (pintype "input"))
      (node (ref "JP401") (pin "1") (pinfunction "1_1") (pintype "passive"))
    )
    (net (code "29") (name "Net-(IC401A-X1)") (class "Default")
      (node (ref "IC401") (pin "8") (pinfunction "X1_8") (pintype "input"))
      (node (ref "JP401") (pin "2") (pinfunction "2_2") (pintype "passive"))
    )
    (net (code "30") (name "Net-(IC401A-X2)") (class "Default")
      (node (ref "IC401") (pin "7") (pinfunction "X2_7") (pintype "input"))
      (node (ref "JP401") (pin "3") (pinfunction "3_3") (pintype "passive"))
    )
    (net (code "31") (name "Net-(IC401A-X3)") (class "Default")
      (node (ref "IC401") (pin "6") (pinfunction "X3_6") (pintype "input"))
      (node (ref "JP401") (pin "4") (pinfunction "4_4") (pintype "passive"))
    )
    (net (code "32") (name "Net-(IC401A-X4)") (class "Default")
      (node (ref "IC401") (pin "5") (pinfunction "X4_5") (pintype "input"))
      (node (ref "JP401") (pin "5") (pinfunction "5_5") (pintype "passive"))
    )
    (net (code "33") (name "Net-(IC401A-X5)") (class "Default")
      (node (ref "IC401") (pin "4") (pinfunction "X5_4") (pintype "input"))
      (node (ref "JP401") (pin "6") (pinfunction "6_6") (pintype "passive"))
    )
    (net (code "34") (name "Net-(IC401A-X6)") (class "Default")
      (node (ref "IC401") (pin "3") (pinfunction "X6_3") (pintype "input"))
      (node (ref "JP401") (pin "7") (pinfunction "7_7") (pintype "passive"))
    )
    (net (code "35") (name "Net-(IC401A-X7)") (class "Default")
      (node (ref "IC401") (pin "2") (pinfunction "X7_2") (pintype "input"))
      (node (ref "JP401") (pin "8") (pinfunction "8_8") (pintype "passive"))
    )
    (net (code "36") (name "Net-(IC401A-X8)") (class "Default")
      (node (ref "IC401") (pin "23") (pinfunction "X8_23") (pintype "input"))
      (node (ref "JP402") (pin "3") (pinfunction "3_3") (pintype "passive"))
    )
    (net (code "37") (name "Net-(IC401A-X9)") (class "Default")
      (node (ref "IC401") (pin "22") (pinfunction "X9_22") (pintype "input"))
      (node (ref "JP402") (pin "4") (pinfunction "4_4") (pintype "passive"))
    )
    (net (code "38") (name "Net-(IC401A-X10)") (class "Default")
      (node (ref "IC401") (pin "21") (pinfunction "X10_21") (pintype "input"))
      (node (ref "JP402") (pin "5") (pinfunction "5_5") (pintype "passive"))
    )
    (net (code "39") (name "Net-(IC401A-X11)") (class "Default")
      (node (ref "IC401") (pin "20") (pinfunction "X11_20") (pintype "input"))
      (node (ref "JP402") (pin "6") (pinfunction "6_6") (pintype "passive"))
    )
    (net (code "40") (name "Net-(IC401A-X12)") (class "Default")
      (node (ref "IC401") (pin "19") (pinfunction "X12_19") (pintype "input"))
      (node (ref "JP402") (pin "7") (pinfunction "7_7") (pintype "passive"))
    )
    (net (code "41") (name "Net-(IC401A-X13)") (class "Default")
      (node (ref "IC401") (pin "18") (pinfunction "X13_18") (pintype "input"))
      (node (ref "JP402") (pin "8") (pinfunction "8_8") (pintype "passive"))
    )
    (net (code "42") (name "Net-(IC401A-X14)") (class "Default")
      (node (ref "IC401") (pin "17") (pinfunction "X14_17") (pintype "input"))
      (node (ref "JP402") (pin "9") (pinfunction "9_9") (pintype "passive"))
    )
    (net (code "43") (name "Net-(IC401A-X15)") (class "Default")
      (node (ref "IC401") (pin "16") (pinfunction "X15_16") (pintype "input"))
      (node (ref "JP402") (pin "10") (pinfunction "10_10") (pintype "passive"))
    )
    (net (code "44") (name "Net-(IC402A-Q2)") (class "Default")
      (node (ref "IC402") (pin "7") (pinfunction "Q2_7") (pintype "output"))
      (node (ref "SJ401") (pin "1") (pinfunction "1_1") (pintype "passive"))
    )
    (net (code "45") (name "Net-(IC402A-Q3)") (class "Default")
      (node (ref "IC402") (pin "6") (pinfunction "Q3_6") (pintype "output"))
      (node (ref "SJ402") (pin "1") (pinfunction "1_1") (pintype "passive"))
    )
    (net (code "46") (name "Net-(IC402A-Q4)") (class "Default")
      (node (ref "IC402") (pin "5") (pinfunction "Q4_5") (pintype "output"))
      (node (ref "SJ403") (pin "1") (pinfunction "1_1") (pintype "passive"))
    )
    (net (code "47") (name "Net-(IC502-PadD5)") (class "Default")
      (node (ref "IC502") (pin "D5") (pinfunction "D5_D5") (pintype "bidirectional"))
      (node (ref "SJ401") (pin "2") (pinfunction "2_2") (pintype "passive"))
      (node (ref "SJ402") (pin "2") (pinfunction "2_2") (pintype "passive"))
      (node (ref "SJ403") (pin "2") (pinfunction "2_2") (pintype "passive"))
    )
    (net (code "48") (name "Net-(IC502-PadRX1)") (class "Default")
      (node (ref "IC502") (pin "RX1") (pinfunction "RX1_RX1") (pintype "bidirectional"))
      (node (ref "IC503") (pin "GPIO4") (pinfunction "GPIO4_GPIO4") (pintype "bidirectional"))
    )
    (net (code "49") (name "Net-(IC502-PadTX0)") (class "Default")
      (node (ref "IC502") (pin "TX0") (pinfunction "TX0_TX0") (pintype "bidirectional"))
      (node (ref "R1") (pin "1") (pinfunction "1_1") (pintype "passive"))
    )
    (net (code "50") (name "Net-(IC503-PadGPIO0)") (class "Default")
      (node (ref "IC503") (pin "GPIO0") (pinfunction "GPIO0_GPIO0") (pintype "bidirectional"))
      (node (ref "JP503") (pin "1") (pinfunction "1_1") (pintype "passive"))
    )
    (net (code "51") (name "Net-(IC503-PadGPIO5)") (class "Default")
      (node (ref "IC503") (pin "GPIO5") (pinfunction "GPIO5_GPIO5") (pintype "bidirectional"))
      (node (ref "R1") (pin "2") (pinfunction "2_2") (pintype "passive"))
      (node (ref "R2") (pin "1") (pinfunction "1_1") (pintype "passive"))
    )
    (net (code "52") (name "Net-(IC503-PadGPIO12)") (class "Default")
      (node (ref "IC503") (pin "GPIO12") (pinfunction "GPIO12_GPIO12") (pintype "bidirectional"))
      (node (ref "JP2") (pin "1") (pinfunction "1_1") (pintype "passive"))
    )
    (net (code "53") (name "Net-(IC503-PadRESET)") (class "Default")
      (node (ref "IC503") (pin "RESET") (pinfunction "RESET_RESET") (pintype "bidirectional"))
      (node (ref "R501") (pin "1") (pinfunction "1_1") (pintype "passive"))
    )
    (net (code "54") (name "Net-(IC503-RX)") (class "Default")
      (node (ref "IC503") (pin "RXD0") (pinfunction "RX_RXD0") (pintype "bidirectional"))
      (node (ref "JP502") (pin "3") (pinfunction "3_3") (pintype "passive"))
    )
    (net (code "55") (name "Net-(IC503-TX)") (class "Default")
      (node (ref "IC503") (pin "TXD0") (pinfunction "TX_TXD0") (pintype "bidirectional"))
      (node (ref "JP502") (pin "2") (pinfunction "2_2") (pintype "passive"))
    )
    (net (code "56") (name "Net-(Q101-G)") (class "Default")
      (node (ref "IC502") (pin "D2") (pinfunction "D2_D2") (pintype "bidirectional"))
      (node (ref "Q101") (pin "4") (pinfunction "G_4") (pintype "passive"))
      (node (ref "R101") (pin "1") (pinfunction "1_1") (pintype "passive"))
    )
    (net (code "57") (name "Net-(Q102-G)") (class "Default")
      (node (ref "IC502") (pin "D3") (pinfunction "D3_D3") (pintype "bidirectional"))
      (node (ref "Q102") (pin "4") (pinfunction "G_4") (pintype "passive"))
      (node (ref "R102") (pin "1") (pinfunction "1_1") (pintype "passive"))
    )
    (net (code "58") (name "Net-(Q103-G)") (class "Default")
      (node (ref "IC502") (pin "D4") (pinfunction "D4_D4") (pintype "bidirectional"))
      (node (ref "Q103") (pin "4") (pinfunction "G_4") (pintype "passive"))
      (node (ref "R103") (pin "1") (pinfunction "1_1") (pintype "passive"))
    )
    (net (code "59") (name "Net-(Q104-G)") (class "Default")
      (node (ref "IC502") (pin "D6") (pinfunction "D6_D6") (pintype "bidirectional"))
      (node (ref "Q104") (pin "4") (pinfunction "G_4") (pintype "passive"))
      (node (ref "R104") (pin "1") (pinfunction "1_1") (pintype "passive"))
    )
    (net (code "60") (name "Net-(Q105-G)") (class "Default")
      (node (ref "IC502") (pin "D7") (pinfunction "D7_D7") (pintype "bidirectional"))
      (node (ref "Q105") (pin "4") (pinfunction "G_4") (pintype "passive"))
      (node (ref "R105") (pin "1") (pinfunction "1_1") (pintype "passive"))
    )
    (net (code "61") (name "Net-(Q401-D)") (class "Default")
      (node (ref "JP401") (pin "9") (pinfunction "9_9") (pintype "passive"))
      (node (ref "JP402") (pin "2") (pinfunction "2_2") (pintype "passive"))
      (node (ref "Q401") (pin "3") (pinfunction "D_3") (pintype "passive"))
    )
    (net (code "62") (name "Net-(Q401-G)") (class "Default")
      (node (ref "IC502") (pin "D8") (pinfunction "D8_D8") (pintype "bidirectional"))
      (node (ref "Q401") (pin "1") (pinfunction "G_1") (pintype "passive"))
      (node (ref "R401") (pin "2") (pinfunction "2_2") (pintype "passive"))
    )
    (net (code "63") (name "V+") (class "Default")
      (node (ref "C101") (pin "1") (pinfunction "1_1") (pintype "passive"))
      (node (ref "C102") (pin "1") (pinfunction "1_1") (pintype "passive"))
      (node (ref "C103") (pin "1") (pinfunction "1_1") (pintype "passive"))
      (node (ref "C104") (pin "1") (pinfunction "1_1") (pintype "passive"))
      (node (ref "C105") (pin "1") (pinfunction "1_1") (pintype "passive"))
      (node (ref "C106") (pin "+") (pinfunction "+_+") (pintype "passive"))
      (node (ref "C107") (pin "+") (pinfunction "+_+") (pintype "passive"))
      (node (ref "C201") (pin "1") (pinfunction "1_1") (pintype "passive"))
      (node (ref "C202") (pin "1") (pinfunction "1_1") (pintype "passive"))
      (node (ref "D106") (pin "C") (pinfunction "C_C") (pintype "passive"))
      (node (ref "D107") (pin "C") (pinfunction "C_C") (pintype "passive"))
      (node (ref "D108") (pin "C") (pinfunction "C_C") (pintype "passive"))
      (node (ref "D109") (pin "C") (pinfunction "C_C") (pintype "passive"))
      (node (ref "D110") (pin "C") (pinfunction "C_C") (pintype "passive"))
      (node (ref "IC201") (pin "4") (pinfunction "EN_4") (pintype "bidirectional"))
      (node (ref "IC201") (pin "5") (pinfunction "VIN_5") (pintype "power_in"))
      (node (ref "IC303") (pin "7") (pinfunction "VIN-_7") (pintype "input"))
      (node (ref "J102") (pin "A1") (pinfunction "1_A1") (pintype "passive"))
      (node (ref "J102") (pin "A2") (pinfunction "1_A2") (pintype "passive"))
      (node (ref "J104") (pin "A1") (pinfunction "1_A1") (pintype "passive"))
      (node (ref "J104") (pin "A2") (pinfunction "1_A2") (pintype "passive"))
      (node (ref "J106") (pin "A1") (pinfunction "1_A1") (pintype "passive"))
      (node (ref "J106") (pin "A2") (pinfunction "1_A2") (pintype "passive"))
      (node (ref "J108") (pin "A1") (pinfunction "1_A1") (pintype "passive"))
      (node (ref "J108") (pin "A2") (pinfunction "1_A2") (pintype "passive"))
      (node (ref "J110") (pin "A1") (pinfunction "1_A1") (pintype "passive"))
      (node (ref "J110") (pin "A2") (pinfunction "1_A2") (pintype "passive"))
      (node (ref "R310") (pin "2") (pinfunction "2_2") (pintype "passive"))
    )
    (net (code "64") (name "VCC") (class "Default")
      (node (ref "C204") (pin "1") (pinfunction "1_1") (pintype "passive"))
      (node (ref "C205") (pin "1") (pinfunction "1_1") (pintype "passive"))
      (node (ref "C301") (pin "1") (pinfunction "1_1") (pintype "passive"))
      (node (ref "C302") (pin "1") (pinfunction "1_1") (pintype "passive"))
      (node (ref "C401") (pin "1") (pinfunction "1_1") (pintype "passive"))
      (node (ref "C402") (pin "1") (pinfunction "1_1") (pintype "passive"))
      (node (ref "C403") (pin "1") (pinfunction "1_1") (pintype "passive"))
      (node (ref "C501") (pin "1") (pinfunction "1_1") (pintype "passive"))
      (node (ref "C503") (pin "1") (pinfunction "1_1") (pintype "passive"))
      (node (ref "D202") (pin "A") (pinfunction "A_A") (pintype "passive"))
      (node (ref "IC302") (pin "1") (pinfunction "A1_1") (pintype "input"))
      (node (ref "IC302") (pin "2") (pinfunction "A0_2") (pintype "input"))
      (node (ref "IC302") (pin "5") (pinfunction "VS_5") (pintype "power_in"))
      (node (ref "IC303") (pin "5") (pinfunction "VS_5") (pintype "power_in"))
      (node (ref "IC401") (pin "24") (pinfunction "VDD_24") (pintype "power_in"))
      (node (ref "IC402") (pin "16") (pinfunction "VDD_16") (pintype "power_in"))
      (node (ref "IC501") (pin "8") (pinfunction "VCC_8") (pintype "power_in"))
      (node (ref "IC502") (pin "5V") (pinfunction "5.5V_5V") (pintype "bidirectional"))
      (node (ref "IC504") (pin "3") (pinfunction "IN_3") (pintype "input"))
      (node (ref "JP1") (pin "1") (pinfunction "1_1") (pintype "passive"))
      (node (ref "JP502") (pin "1") (pinfunction "1_1") (pintype "passive"))
      (node (ref "L201") (pin "2") (pinfunction "2_2") (pintype "passive"))
      (node (ref "Q401") (pin "2") (pinfunction "S_2") (pintype "passive"))
      (node (ref "R201") (pin "1") (pinfunction "1_1") (pintype "passive"))
      (node (ref "R401") (pin "1") (pinfunction "1_1") (pintype "passive"))
      (node (ref "R502") (pin "1") (pinfunction "1_1") (pintype "passive"))
      (node (ref "R503") (pin "1") (pinfunction "1_1") (pintype "passive"))
    )
    (net (code "65") (name "unconnected-(IC402A-Q1-Pad9)") (class "Default")
      (node (ref "IC402") (pin "9") (pinfunction "Q1_9") (pintype "output"))
    )
    (net (code "66") (name "unconnected-(IC402A-Q5-Pad3)") (class "Default")
      (node (ref "IC402") (pin "3") (pinfunction "Q5_3") (pintype "output"))
    )
    (net (code "67") (name "unconnected-(IC402A-Q6-Pad2)") (class "Default")
      (node (ref "IC402") (pin "2") (pinfunction "Q6_2") (pintype "output"))
    )
    (net (code "68") (name "unconnected-(IC402A-Q7-Pad4)") (class "Default")
      (node (ref "IC402") (pin "4") (pinfunction "Q7_4") (pintype "output"))
    )
    (net (code "69") (name "unconnected-(IC402A-Q8-Pad13)") (class "Default")
      (node (ref "IC402") (pin "13") (pinfunction "Q8_13") (pintype "output"))
    )
    (net (code "70") (name "unconnected-(IC402A-Q9-Pad12)") (class "Default")
      (node (ref "IC402") (pin "12") (pinfunction "Q9_12") (pintype "output"))
    )
    (net (code "71") (name "unconnected-(IC402A-Q10-Pad14)") (class "Default")
      (node (ref "IC402") (pin "14") (pinfunction "Q10_14") (pintype "output"))
    )
    (net (code "72") (name "unconnected-(IC402A-Q11-Pad15)") (class "Default")
      (node (ref "IC402") (pin "15") (pinfunction "Q11_15") (pintype "output"))
    )
    (net (code "73") (name "unconnected-(IC402A-Q12-Pad1)") (class "Default")
      (node (ref "IC402") (pin "1") (pinfunction "Q12_1") (pintype "output"))
    )
    (net (code "74") (name "unconnected-(IC501-OS-Pad3)") (class "Default")
      (node (ref "IC501") (pin "3") (pinfunction "OS_3") (pintype "output"))
    )
    (net (code "75") (name "unconnected-(IC502-GND2-PadGND1)") (class "Default")
      (node (ref "IC502") (pin "GND1") (pinfunction "GND2_GND1") (pintype "bidirectional"))
    )
    (net (code "76") (name "unconnected-(IC502-Pad3.3V)") (class "Default")
      (node (ref "IC502") (pin "3.3V") (pinfunction "3.3V_3.3V") (pintype "bidirectional"))
    )
    (net (code "77") (name "unconnected-(IC502-PadA0)") (class "Default")
      (node (ref "IC502") (pin "A0") (pinfunction "A0_A0") (pintype "bidirectional"))
    )
    (net (code "78") (name "unconnected-(IC502-PadA1)") (class "Default")
      (node (ref "IC502") (pin "A1") (pinfunction "A1_A1") (pintype "bidirectional"))
    )
    (net (code "79") (name "unconnected-(IC502-PadA2)") (class "Default")
      (node (ref "IC502") (pin "A2") (pinfunction "A2_A2") (pintype "bidirectional"))
    )
    (net (code "80") (name "unconnected-(IC502-PadA3)") (class "Default")
      (node (ref "IC502") (pin "A3") (pinfunction "A3_A3") (pintype "bidirectional"))
    )
    (net (code "81") (name "unconnected-(IC502-PadA6)") (class "Default")
      (node (ref "IC502") (pin "A6") (pinfunction "A6_A6") (pintype "bidirectional"))
    )
    (net (code "82") (name "unconnected-(IC502-PadA7)") (class "Default")
      (node (ref "IC502") (pin "A7") (pinfunction "A7_A7") (pintype "bidirectional"))
    )
    (net (code "83") (name "unconnected-(IC502-PadAREF)") (class "Default")
      (node (ref "IC502") (pin "AREF") (pinfunction "AREF_AREF") (pintype "bidirectional"))
    )
    (net (code "84") (name "unconnected-(IC502-PadD13)") (class "Default")
      (node (ref "IC502") (pin "D13") (pinfunction "D13_D13") (pintype "bidirectional"))
    )
    (net (code "85") (name "unconnected-(IC502-PadICSP1)") (class "Default")
      (node (ref "IC502") (pin "ICSP1") (pinfunction "ICSP1_ICSP1") (pintype "bidirectional"))
    )
    (net (code "86") (name "unconnected-(IC502-PadICSP2)") (class "Default")
      (node (ref "IC502") (pin "ICSP2") (pinfunction "ICSP2_ICSP2") (pintype "bidirectional"))
    )
    (net (code "87") (name "unconnected-(IC502-PadICSP3)") (class "Default")
      (node (ref "IC502") (pin "ICSP3") (pinfunction "ICSP3_ICSP3") (pintype "bidirectional"))
    )
    (net (code "88") (name "unconnected-(IC502-PadICSP4)") (class "Default")
      (node (ref "IC502") (pin "ICSP4") (pinfunction "ICSP4_ICSP4") (pintype "bidirectional"))
    )
    (net (code "89") (name "unconnected-(IC502-PadICSP5)") (class "Default")
      (node (ref "IC502") (pin "ICSP5") (pinfunction "ICSP5_ICSP5") (pintype "bidirectional"))
    )
    (net (code "90") (name "unconnected-(IC502-PadICSP6)") (class "Default")
      (node (ref "IC502") (pin "ICSP6") (pinfunction "ICSP6_ICSP6") (pintype "bidirectional"))
    )
    (net (code "91") (name "unconnected-(IC502-PadRAW)") (class "Default")
      (node (ref "IC502") (pin "RAW") (pinfunction "RAW_RAW") (pintype "bidirectional"))
    )
    (net (code "92") (name "unconnected-(IC502-PadRST)") (class "Default")
      (node (ref "IC502") (pin "RST") (pinfunction "RST_RST") (pintype "bidirectional"))
    )
    (net (code "93") (name "unconnected-(IC502-PadRST1)") (class "Default")
      (node (ref "IC502") (pin "RST1") (pinfunction "RST1_RST1") (pintype "bidirectional"))
    )
    (net (code "94") (name "unconnected-(IC503-PadADC)") (class "Default")
      (node (ref "IC503") (pin "ADC") (pinfunction "ADC_ADC") (pintype "bidirectional"))
    )
    (net (code "95") (name "unconnected-(IC503-PadGPIO13)") (class "Default")
      (node (ref "IC503") (pin "GPIO13") (pinfunction "GPIO13_GPIO13") (pintype "bidirectional"))
    )
    (net (code "96") (name "unconnected-(IC503-PadGPIO14)") (class "Default")
      (node (ref "IC503") (pin "GPIO14") (pinfunction "GPIO14_GPIO14") (pintype "bidirectional"))
    )
    (net (code "97") (name "unconnected-(IC503-PadGPIO15)") (class "Default")
      (node (ref "IC503") (pin "GPIO15") (pinfunction "GPIO15_GPIO15") (pintype "bidirectional"))
    )
    (net (code "98") (name "unconnected-(IC503-PadGPIO16)") (class "Default")
      (node (ref "IC503") (pin "GPIO16") (pinfunction "GPIO16_GPIO16") (pintype "bidirectional"))
    )
  )
)
